# Power_Supply.net
KiCad netlist of a schematic drawn in Altium Designer
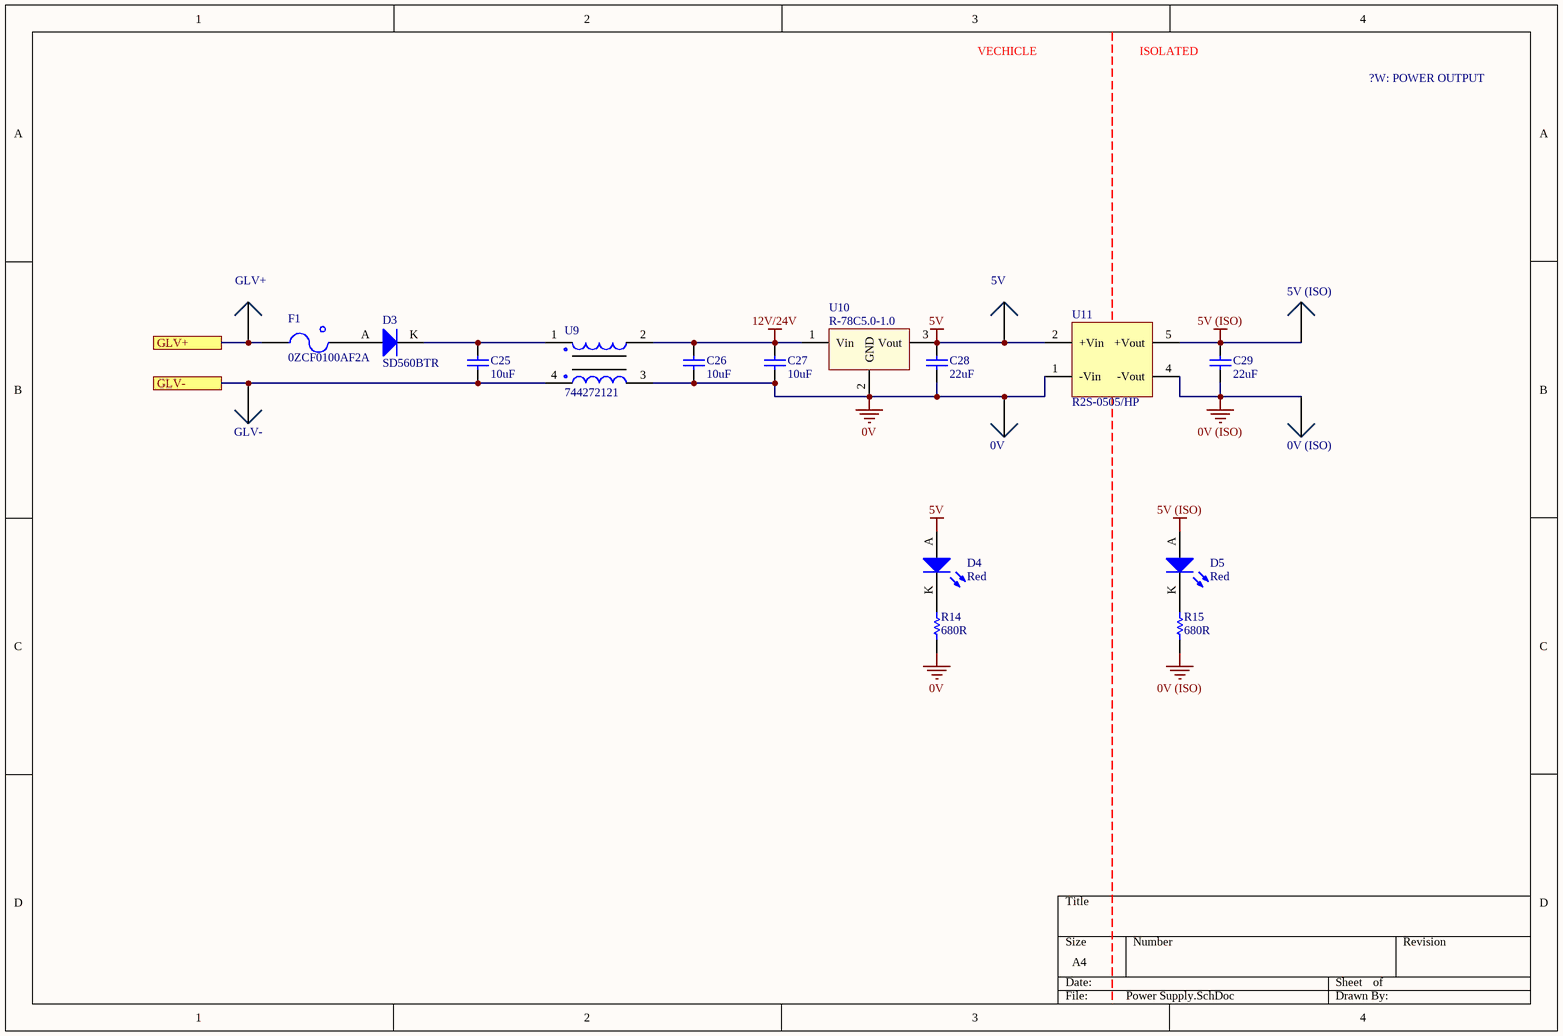
[diagram p0: Power Supply.SchDoc]

(export (version "E")
  (design (tool "Eeschema 10.0.6"))
  (components
    (comp (ref "0V")
      (value "0mm")
      (footprint "SMD Test Point")
      (fields (field (name "PART NUMBER") "SMD Test Point") (field (name "CONTACT") "NA"))
      (libsource (lib "ts_20-standard-connectors") (part "Test Point"))
    )
    (comp (ref "0V (ISO)")
      (value "0mm")
      (footprint "SMD Test Point")
      (fields (field (name "PART NUMBER") "SMD Test Point") (field (name "CONTACT") "NA"))
      (libsource (lib "ts_20-standard-connectors") (part "Test Point"))
    )
    (comp (ref "5V")
      (value "0mm")
      (footprint "SMD Test Point")
      (fields (field (name "PART NUMBER") "SMD Test Point") (field (name "CONTACT") "NA"))
      (libsource (lib "ts_20-standard-connectors") (part "Test Point"))
    )
    (comp (ref "5V (ISO)")
      (value "0mm")
      (footprint "SMD Test Point")
      (fields (field (name "PART NUMBER") "SMD Test Point") (field (name "CONTACT") "NA"))
      (libsource (lib "ts_20-standard-connectors") (part "Test Point"))
    )
    (comp (ref "C25")
      (value "10uF")
      (footprint "0805")
      (fields
        (field (name "PART NUMBER") "GRM21BR6YA106KE43L")
        (field (name "TOLERANCE") "10%")
        (field (name "MANUFACTURER") "muRata")
      )
      (libsource (lib "ts_20-standard-library") (part "Capacitor"))
    )
    (comp (ref "C26")
      (value "10uF")
      (footprint "0805")
      (fields
        (field (name "PART NUMBER") "GRM21BR6YA106KE43L")
        (field (name "TOLERANCE") "10%")
        (field (name "MANUFACTURER") "muRata")
      )
      (libsource (lib "ts_20-standard-library") (part "Capacitor"))
    )
    (comp (ref "C27")
      (value "10uF")
      (footprint "0805")
      (fields
        (field (name "PART NUMBER") "GRM21BR6YA106KE43L")
        (field (name "TOLERANCE") "10%")
        (field (name "MANUFACTURER") "muRata")
      )
      (libsource (lib "ts_20-standard-library") (part "Capacitor"))
    )
    (comp (ref "C28")
      (value "22uF")
      (footprint "1206")
      (fields
        (field (name "PART NUMBER") "CC1206MKX5R7BB226")
        (field (name "TOLERANCE") "20%")
        (field (name "MANUFACTURER") "YAGEO")
      )
      (libsource (lib "ts_20-standard-library") (part "Capacitor"))
    )
    (comp (ref "C29")
      (value "22uF")
      (footprint "1206")
      (fields
        (field (name "PART NUMBER") "CC1206MKX5R7BB226")
        (field (name "TOLERANCE") "20%")
        (field (name "MANUFACTURER") "YAGEO")
      )
      (libsource (lib "ts_20-standard-library") (part "Capacitor"))
    )
    (comp (ref "D3")
      (value "SD560BTR")
      (footprint "SMB Diode")
      (description "1.2V_F 600V 5A SMB")
      (fields
        (field (name "MANUFACTURER") "SMC Diode Solutions")
        (field (name "DIGIKEY PART NUMBER") "1655-1530-2-ND")
      )
      (libsource (lib "ts_20-standard-library") (part "Diode"))
    )
    (comp (ref "D4")
      (value "Red")
      (footprint "0805 LED")
      (description "Red LED Indication - Discrete 1.75V 0805 (2012 Metric)")
      (fields (field (name "PART NUMBER") "SML-210LTT86") (field (name "MANUFACTURER") "ROHM Semiconductor"))
      (libsource (lib "ts_20-standard-library") (part "LED"))
    )
    (comp (ref "D5")
      (value "Red")
      (footprint "0805 LED")
      (description "Red LED Indication - Discrete 1.75V 0805 (2012 Metric)")
      (fields (field (name "PART NUMBER") "SML-210LTT86") (field (name "MANUFACTURER") "ROHM Semiconductor"))
      (libsource (lib "ts_20-standard-library") (part "LED"))
    )
    (comp (ref "F1")
      (value "0ZCF0100AF2A")
      (footprint "2920")
      (description "PTC RESET FUSE 60V 1A 292")
      (fields
        (field (name "MANUFACTURER") "Littelfuse Inc.")
        (field (name "DIGIKEY PART NUMBER") "507-2070-1-ND")
      )
      (libsource (lib "ts_20-standard-library") (part "PTC Fuse"))
    )
    (comp (ref "GLV+")
      (value "0mm")
      (footprint "SMD Test Point")
      (fields (field (name "PART NUMBER") "SMD Test Point") (field (name "CONTACT") "NA"))
      (libsource (lib "ts_20-standard-connectors") (part "Test Point"))
    )
    (comp (ref "GLV-")
      (value "0mm")
      (footprint "SMD Test Point")
      (fields (field (name "PART NUMBER") "SMD Test Point") (field (name "CONTACT") "NA"))
      (libsource (lib "ts_20-standard-connectors") (part "Test Point"))
    )
    (comp (ref "R14")
      (value "680R")
      (footprint "0805")
      (fields
        (field (name "PART NUMBER") "RC0805FR07680RL")
        (field (name "MANUFACTURER") "YAGEO")
        (field (name "TOLERANCE") "0.01")
      )
      (libsource (lib "ts_20-standard-library") (part "Resistor"))
    )
    (comp (ref "R15")
      (value "680R")
      (footprint "0805")
      (fields
        (field (name "PART NUMBER") "RC0805FR07680RL")
        (field (name "MANUFACTURER") "YAGEO")
        (field (name "TOLERANCE") "0.01")
      )
      (libsource (lib "ts_20-standard-library") (part "Resistor"))
    )
    (comp (ref "U9")
      (value "744272121")
      (footprint "Wurth 4-PC Pad")
      (description "120µH @ 100kHz 2 Line Common Mode Choke Surface Mount 460 Ohms @ 30MHz 2.5A DCR 25mOhm")
      (fields
        (field (name "MANUFACTURER") "Wurth Electronics Inc")
        (field (name "DIGIKEY PART NUMBER") "732-1489-1-ND")
      )
      (libsource (lib "ts_20-standard-library") (part "744272121"))
    )
    (comp (ref "U10")
      (value "R-78C5.0-1.0")
      (footprint "RECOM 3-SIP")
      (description "CONV DC/DC 1A 5V OUT SIP VERT")
      (fields (field (name "MANUFACTURER") "Recom") (field (name "DIGIKEY PART NUMBER") "945-1395-5-ND"))
      (libsource (lib "ts_20-standard-library") (part "R-78C5.0-1.0"))
    )
    (comp (ref "U11")
      (value "R2S-0505/HP")
      (footprint "RECOM 8-SMD (5 Pin)")
      (description "Isolated Module DC DC Converter 1 Output 3.3V 606mA 4.5V - 5.5V Input")
      (fields (field (name "MANUFACTURER") "Recom") (field (name "DIGIKEY PART NUMBER") "945-1764-5-ND"))
      (libsource (lib "ts_20-standard-library") (part "R2S-0505/HP"))
    )
  )
  (nets
    (net (code "1") (name "/GLV+") (class "Default")
      (node (ref "F1") (pin "1") (pinfunction "1_1") (pintype "passive"))
      (node (ref "GLV+") (pin "1") (pinfunction "1_1") (pintype "passive"))
    )
    (net (code "2") (name "/GLV-") (class "Default")
      (node (ref "C25") (pin "1") (pinfunction "1_1") (pintype "passive"))
      (node (ref "GLV-") (pin "1") (pinfunction "1_1") (pintype "passive"))
      (node (ref "U9") (pin "4") (pinfunction "4_4") (pintype "passive"))
    )
    (net (code "3") (name "0V") (class "Default")
      (node (ref "0V") (pin "1") (pinfunction "1_1") (pintype "passive"))
      (node (ref "C26") (pin "1") (pinfunction "1_1") (pintype "passive"))
      (node (ref "C27") (pin "1") (pinfunction "1_1") (pintype "passive"))
      (node (ref "C28") (pin "1") (pinfunction "1_1") (pintype "passive"))
      (node (ref "R14") (pin "1") (pinfunction "1_1") (pintype "passive"))
      (node (ref "U10") (pin "2") (pinfunction "GND_2") (pintype "passive"))
      (node (ref "U11") (pin "1") (pinfunction "-Vin_1") (pintype "power_in"))
      (node (ref "U9") (pin "3") (pinfunction "3_3") (pintype "power_in"))
    )
    (net (code "4") (name "0V (ISO)") (class "Default")
      (node (ref "0V (ISO)") (pin "1") (pinfunction "1_1") (pintype "passive"))
      (node (ref "C29") (pin "1") (pinfunction "1_1") (pintype "passive"))
      (node (ref "R15") (pin "1") (pinfunction "1_1") (pintype "passive"))
      (node (ref "U11") (pin "4") (pinfunction "-Vout_4") (pintype "power_in"))
    )
    (net (code "5") (name "5V") (class "Default")
      (node (ref "5V") (pin "1") (pinfunction "1_1") (pintype "passive"))
      (node (ref "C28") (pin "2") (pinfunction "2_2") (pintype "passive"))
      (node (ref "D4") (pin "A") (pinfunction "A_A") (pintype "passive"))
      (node (ref "U10") (pin "3") (pinfunction "Vout_3") (pintype "passive"))
      (node (ref "U11") (pin "2") (pinfunction "+Vin_2") (pintype "power_in"))
    )
    (net (code "6") (name "5V (ISO)") (class "Default")
      (node (ref "5V (ISO)") (pin "1") (pinfunction "1_1") (pintype "passive"))
      (node (ref "C29") (pin "2") (pinfunction "2_2") (pintype "passive"))
      (node (ref "D5") (pin "A") (pinfunction "A_A") (pintype "passive"))
      (node (ref "U11") (pin "5") (pinfunction "+Vout_5") (pintype "power_in"))
    )
    (net (code "7") (name "12V{slash}24V") (class "Default")
      (node (ref "C26") (pin "2") (pinfunction "2_2") (pintype "passive"))
      (node (ref "C27") (pin "2") (pinfunction "2_2") (pintype "passive"))
      (node (ref "U10") (pin "1") (pinfunction "Vin_1") (pintype "passive"))
      (node (ref "U9") (pin "2") (pinfunction "2_2") (pintype "passive"))
    )
    (net (code "8") (name "Net-(C25-Pad2)") (class "Default")
      (node (ref "C25") (pin "2") (pinfunction "2_2") (pintype "passive"))
      (node (ref "D3") (pin "K") (pinfunction "K_K") (pintype "passive"))
      (node (ref "U9") (pin "1") (pinfunction "1_1") (pintype "passive"))
    )
    (net (code "9") (name "Net-(D3-PadA)") (class "Default")
      (node (ref "D3") (pin "A") (pinfunction "A_A") (pintype "passive"))
      (node (ref "F1") (pin "2") (pinfunction "2_2") (pintype "passive"))
    )
    (net (code "10") (name "Net-(D4-PadK)") (class "Default")
      (node (ref "D4") (pin "K") (pinfunction "K_K") (pintype "passive"))
      (node (ref "R14") (pin "2") (pinfunction "2_2") (pintype "passive"))
    )
    (net (code "11") (name "Net-(D5-PadK)") (class "Default")
      (node (ref "D5") (pin "K") (pinfunction "K_K") (pintype "passive"))
      (node (ref "R15") (pin "2") (pinfunction "2_2") (pintype "passive"))
    )
  )
)
